# logicBlocks-AND.net
KiCad netlist of a schematic drawn in EAGLE
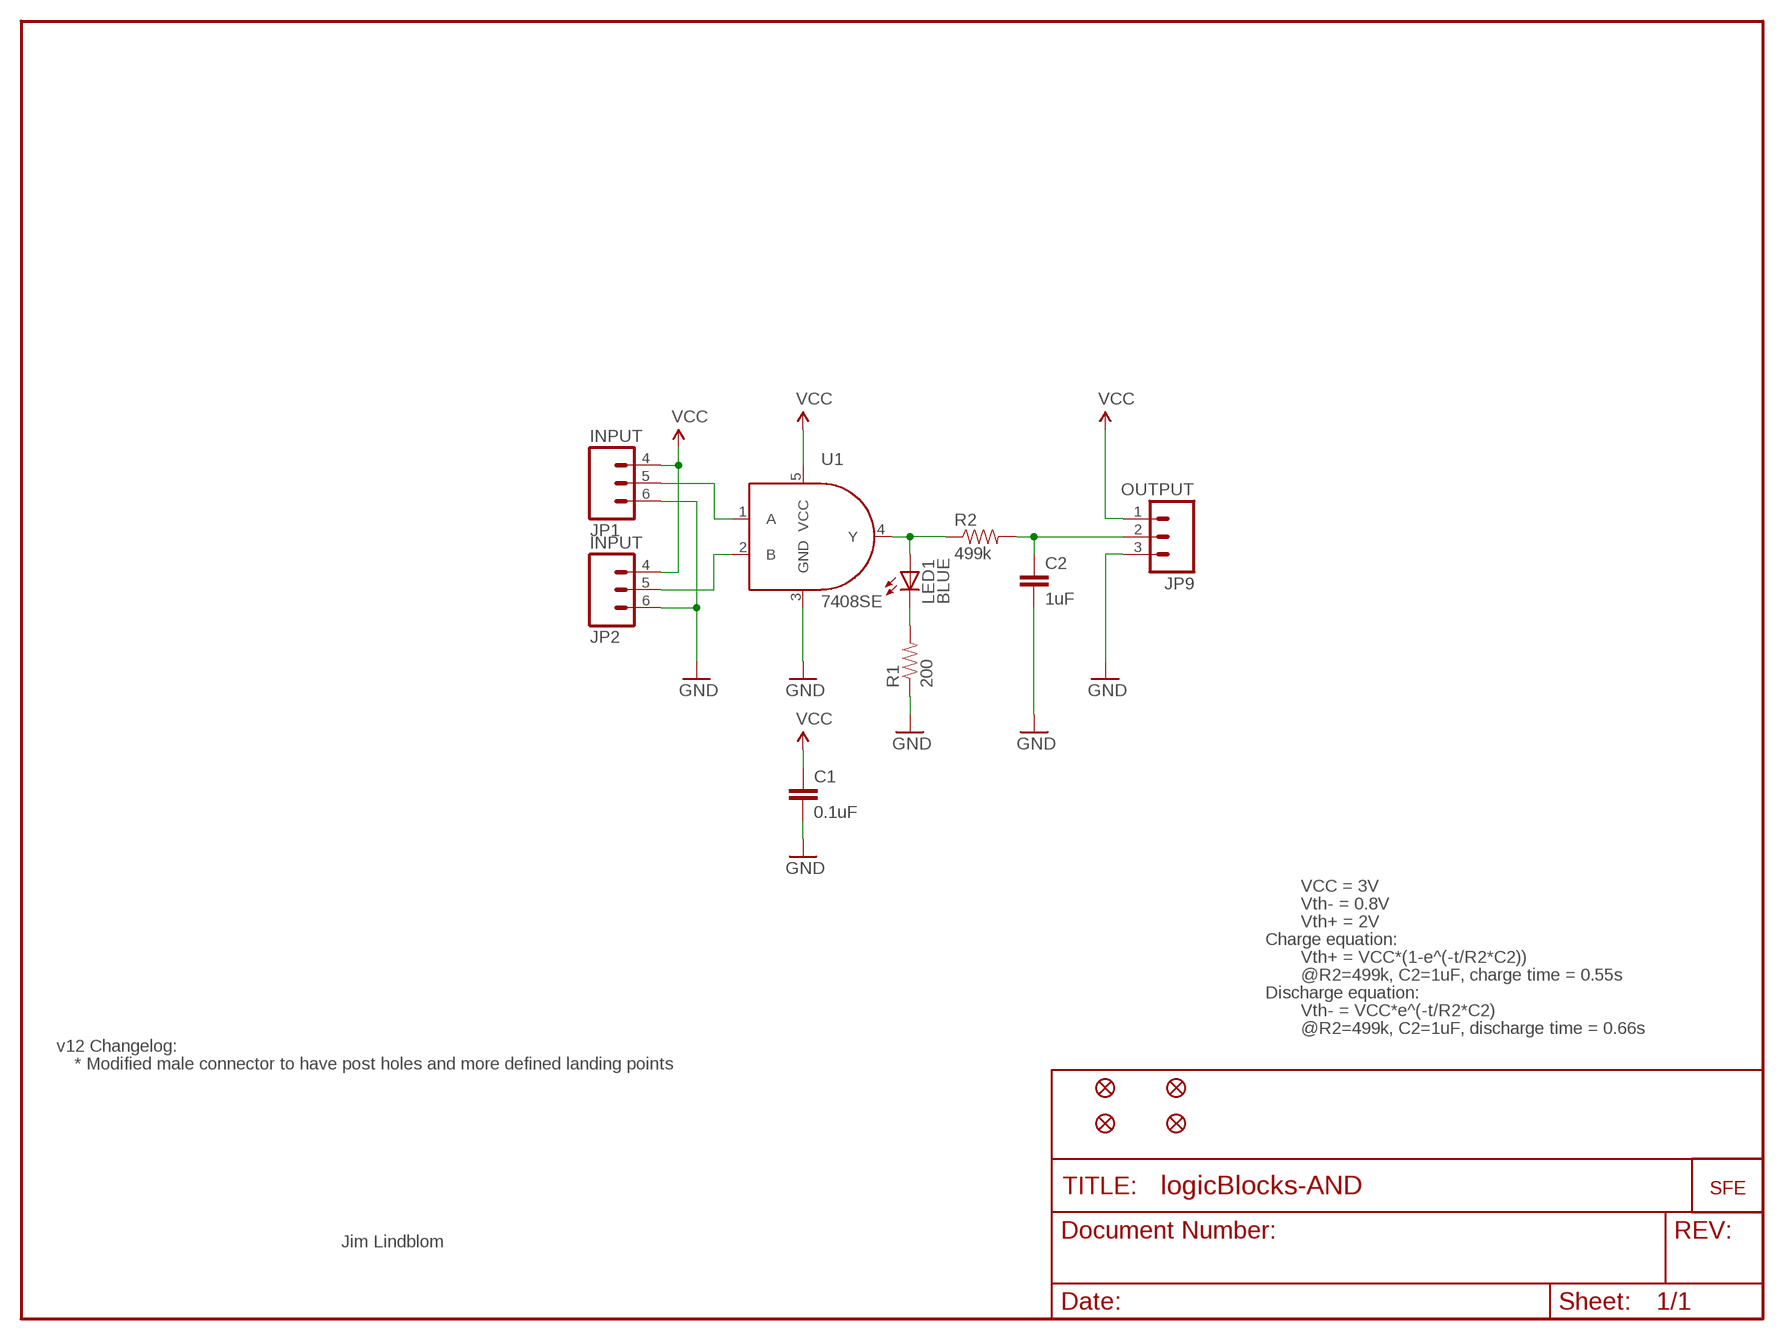
[diagram p0: schematic, sheet 1]

(export (version "E")
  (design (tool "Eeschema 10.0.6"))
  (components
    (comp (ref "C1")
      (value "0.1uF")
      (footprint "eagle-import:0402-CAP")
      (libsource (lib "eagle-import") (part "CAP0402-CAP"))
    )
    (comp (ref "C2")
      (value "1uF")
      (footprint "eagle-import:0402-CAP")
      (libsource (lib "eagle-import") (part "CAP0402-CAP"))
    )
    (comp (ref "JP1")
      (value "INPUT")
      (footprint "eagle-import:1X03-SMD-FEMALE")
      (libsource (lib "eagle-import") (part "M03SMD-RA-FEMALE"))
    )
    (comp (ref "JP2")
      (value "INPUT")
      (footprint "eagle-import:1X03-SMD-FEMALE")
      (libsource (lib "eagle-import") (part "M03SMD-RA-FEMALE"))
    )
    (comp (ref "JP4")
      (value "FIDUCIALUFIDUCIAL")
      (footprint "eagle-import:MICRO-FIDUCIAL")
      (libsource (lib "eagle-import") (part "FIDUCIALUFIDUCIAL"))
    )
    (comp (ref "JP5")
      (value "LOGO-SFESK")
      (footprint "eagle-import:SFE-LOGO-FLAME")
      (libsource (lib "eagle-import") (part "LOGO-SFESK"))
    )
    (comp (ref "JP6")
      (value "FIDUCIALUFIDUCIAL")
      (footprint "eagle-import:MICRO-FIDUCIAL")
      (libsource (lib "eagle-import") (part "FIDUCIALUFIDUCIAL"))
    )
    (comp (ref "JP7")
      (value "FIDUCIALUFIDUCIAL")
      (footprint "eagle-import:MICRO-FIDUCIAL")
      (libsource (lib "eagle-import") (part "FIDUCIALUFIDUCIAL"))
    )
    (comp (ref "JP8")
      (value "FIDUCIALUFIDUCIAL")
      (footprint "eagle-import:MICRO-FIDUCIAL")
      (libsource (lib "eagle-import") (part "FIDUCIALUFIDUCIAL"))
    )
    (comp (ref "JP9")
      (value "OUTPUT")
      (footprint "eagle-import:1X03_SMD_RA_MALE_POST")
      (libsource (lib "eagle-import") (part "M03SMD_RA_MALE_POST"))
    )
    (comp (ref "LED1")
      (value "BLUE")
      (footprint "eagle-import:LED-1206")
      (libsource (lib "eagle-import") (part "LED1206"))
    )
    (comp (ref "R1")
      (value "200")
      (footprint "eagle-import:0402-RES")
      (libsource (lib "eagle-import") (part "RESISTOR0402-RES"))
    )
    (comp (ref "R2")
      (value "499k")
      (footprint "eagle-import:0402-RES")
      (libsource (lib "eagle-import") (part "RESISTOR0402-RES"))
    )
    (comp (ref "U1")
      (value "7408SE")
      (footprint "eagle-import:SOT353")
      (libsource (lib "eagle-import") (part "7408SE"))
    )
  )
  (nets
    (net (code "1") (name "GND") (class "Default")
      (node (ref "C1") (pin "2") (pinfunction "2_2") (pintype "passive"))
      (node (ref "C2") (pin "2") (pinfunction "2_2") (pintype "passive"))
      (node (ref "JP1") (pin "6") (pinfunction "3_6") (pintype "passive"))
      (node (ref "JP2") (pin "6") (pinfunction "3_6") (pintype "passive"))
      (node (ref "JP9") (pin "3") (pinfunction "3_3") (pintype "passive"))
      (node (ref "R1") (pin "1") (pinfunction "1_1") (pintype "passive"))
      (node (ref "U1") (pin "3") (pinfunction "GND_3") (pintype "bidirectional"))
    )
    (net (code "2") (name "Net-(C2-Pad1)") (class "Default")
      (node (ref "C2") (pin "1") (pinfunction "1_1") (pintype "passive"))
      (node (ref "JP9") (pin "2") (pinfunction "2_2") (pintype "passive"))
      (node (ref "R2") (pin "2") (pinfunction "2_2") (pintype "passive"))
    )
    (net (code "3") (name "Net-(JP1-2)") (class "Default")
      (node (ref "JP1") (pin "5") (pinfunction "2_5") (pintype "passive"))
      (node (ref "U1") (pin "1") (pinfunction "A_1") (pintype "bidirectional"))
    )
    (net (code "4") (name "Net-(JP2-2)") (class "Default")
      (node (ref "JP2") (pin "5") (pinfunction "2_5") (pintype "passive"))
      (node (ref "U1") (pin "2") (pinfunction "B_2") (pintype "bidirectional"))
    )
    (net (code "5") (name "Net-(LED1-PadC)") (class "Default")
      (node (ref "LED1") (pin "C") (pinfunction "C_C") (pintype "passive"))
      (node (ref "R1") (pin "2") (pinfunction "2_2") (pintype "passive"))
    )
    (net (code "6") (name "Net-(U1-Y)") (class "Default")
      (node (ref "LED1") (pin "A") (pinfunction "A_A") (pintype "passive"))
      (node (ref "R2") (pin "1") (pinfunction "1_1") (pintype "passive"))
      (node (ref "U1") (pin "4") (pinfunction "Y_4") (pintype "bidirectional"))
    )
    (net (code "7") (name "VCC") (class "Default")
      (node (ref "C1") (pin "1") (pinfunction "1_1") (pintype "passive"))
      (node (ref "JP1") (pin "4") (pinfunction "1_4") (pintype "passive"))
      (node (ref "JP2") (pin "4") (pinfunction "1_4") (pintype "passive"))
      (node (ref "JP9") (pin "1") (pinfunction "1_1") (pintype "passive"))
      (node (ref "U1") (pin "5") (pinfunction "VCC_5") (pintype "bidirectional"))
    )
  )
)
